# MCU.net
KiCad netlist of a schematic drawn in Altium Designer
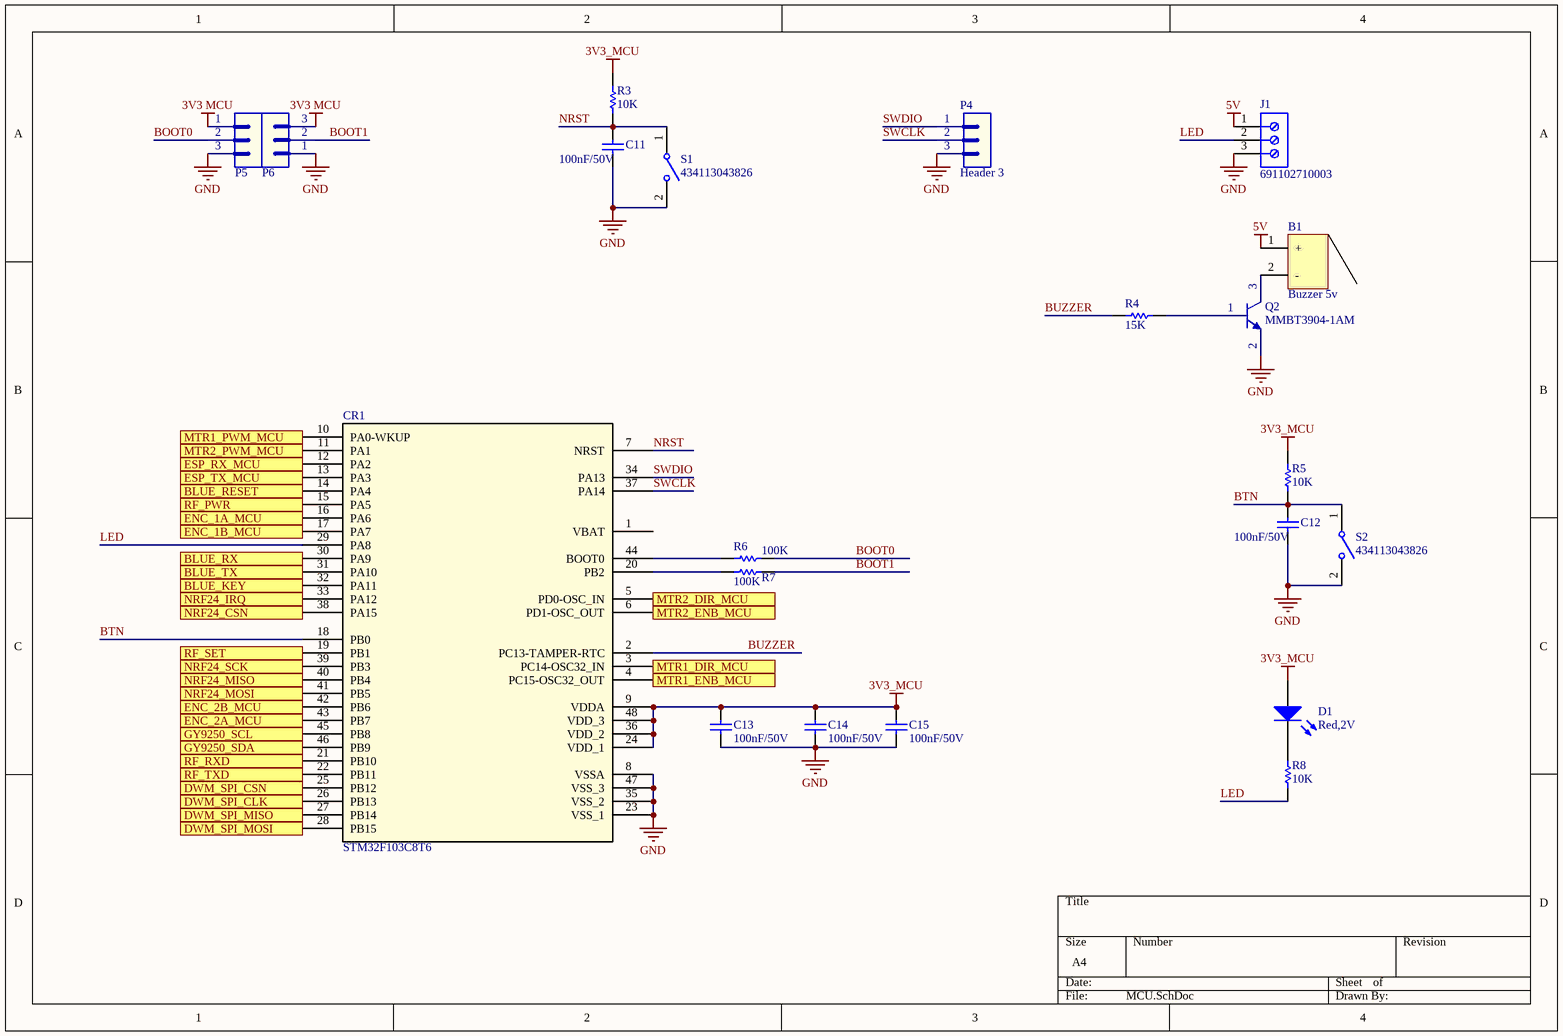
[diagram p0: MCU.SchDoc]

(export (version "E")
  (design (tool "Eeschema 10.0.6"))
  (components
    (comp (ref "B1") (value "Buzzer 5v") (footprint "Buzzer 5v") (libsource (lib "Stm32") (part "Buzzer 5v")))
    (comp (ref "C11")
      (value "100nF/50V")
      (footprint "CAP-SM-0805")
      (description "CAP CER 1000PF 100V X7R 0805")
      (fields
        (field (name "MANUFACTURER") "Johanson Dielectrics Inc.")
        (field (name "MANUFACTURER PART NUMBER") "101X15W102MV4E")
      )
      (libsource (lib "Capacitor") (part "Cap-1nF-50V-0805"))
    )
    (comp (ref "C12")
      (value "100nF/50V")
      (footprint "CAP-SM-0805")
      (description "CAP CER 1000PF 100V X7R 0805")
      (fields
        (field (name "MANUFACTURER") "Johanson Dielectrics Inc.")
        (field (name "MANUFACTURER PART NUMBER") "101X15W102MV4E")
      )
      (libsource (lib "Capacitor") (part "Cap-1nF-50V-0805"))
    )
    (comp (ref "C13")
      (value "100nF/50V")
      (footprint "CAP-SM-0805")
      (description "CAP CER 1000PF 100V X7R 0805")
      (fields
        (field (name "MANUFACTURER") "Johanson Dielectrics Inc.")
        (field (name "MANUFACTURER PART NUMBER") "101X15W102MV4E")
      )
      (libsource (lib "Capacitor") (part "Cap-1nF-50V-0805"))
    )
    (comp (ref "C14")
      (value "100nF/50V")
      (footprint "CAP-SM-0805")
      (description "CAP CER 1000PF 100V X7R 0805")
      (fields
        (field (name "MANUFACTURER") "Johanson Dielectrics Inc.")
        (field (name "MANUFACTURER PART NUMBER") "101X15W102MV4E")
      )
      (libsource (lib "Capacitor") (part "Cap-1nF-50V-0805"))
    )
    (comp (ref "C15")
      (value "100nF/50V")
      (footprint "CAP-SM-0805")
      (description "CAP CER 1000PF 100V X7R 0805")
      (fields
        (field (name "MANUFACTURER") "Johanson Dielectrics Inc.")
        (field (name "MANUFACTURER PART NUMBER") "101X15W102MV4E")
      )
      (libsource (lib "Capacitor") (part "Cap-1nF-50V-0805"))
    )
    (comp (ref "CR1")
      (value "STM32F103C8T6")
      (footprint "STM32F103C8T6")
      (fields (field (name "COPYRIGHT") "Copyright (C) 2018 Accelerated Designs. All rights reserved"))
      (libsource (lib "Schlib1") (part "STM32F103C8T6"))
    )
    (comp (ref "D1")
      (value "Red,2V")
      (footprint "LED-3mm")
      (description "LED RED CLEAR T-1 T/H")
      (fields
        (field (name "MANUFACTURER") "Kingbright")
        (field (name "MANUFACTURER PART NUMBER") "WP710A10SEC/J3")
      )
      (libsource (lib "LED") (part "LED-RED-TH-3mm"))
    )
    (comp (ref "J1")
      (value "691102710003")
      (footprint "691102710003")
      (description "WR-TBL Serie 102 Horizontal Entry Modular, Pressure Clamp, pitch 5mm, 3p")
      (fields (field (name "PUBLISHER") "Wurth Elektronik"))
      (libsource (lib "691101710002_Altium_WR-TBL_rev19a") (part "691102710003"))
    )
    (comp (ref "P4")
      (value "Header 3")
      (footprint "jp3")
      (description "Header, 3-Pin")
      (fields (field (name "PUBLISHER") "Altium Limited"))
      (libsource (lib "") (part "Header 3_1"))
    )
    (comp (ref "P5")
      (value "~")
      (footprint "jp3")
      (description "Header, 3-Pin")
      (fields (field (name "PUBLISHER") "Altium Limited"))
      (libsource (lib "") (part "Header 3_1"))
    )
    (comp (ref "P6")
      (value "~")
      (footprint "jp3")
      (description "Header, 3-Pin")
      (fields (field (name "PUBLISHER") "Altium Limited"))
      (libsource (lib "Integrated_Library_Test") (part "Header 3"))
    )
    (comp (ref "Q2")
      (value "MMBT3904-1AM")
      (footprint "SOT23_NEX")
      (libsource (lib "BJT") (part "MMBT3904-1AM"))
    )
    (comp (ref "R3")
      (value "10K")
      (footprint "Resistor:RES-SM-0805")
      (description "RES 0 OHM JUMPER 0805")
      (fields
        (field (name "MANUFACTURER") "Vishay Dale")
        (field (name "MANUFACTURER PART NUMBER") "WSL080500000ZEA9")
      )
      (libsource (lib "Resistor") (part "Res-0-0805"))
    )
    (comp (ref "R4")
      (value "15K")
      (footprint "Resistor:RES-SM-0805")
      (description "RES 12 KOHM JUMPER 0805")
      (fields
        (field (name "MANUFACTURER") "Vishay Thin Film")
        (field (name "MANUFACTURER PART NUMBER") "PAT0805E3121BST1")
      )
      (libsource (lib "Resistor") (part "Res-12K-0805"))
    )
    (comp (ref "R5")
      (value "10K")
      (footprint "Resistor:RES-SM-0805")
      (description "RES 0 OHM JUMPER 0805")
      (fields
        (field (name "MANUFACTURER") "Vishay Dale")
        (field (name "MANUFACTURER PART NUMBER") "WSL080500000ZEA9")
      )
      (libsource (lib "Resistor") (part "Res-0-0805"))
    )
    (comp (ref "R6")
      (value "100K")
      (footprint "Resistor:RES-SM-0805")
      (description "RES 1K OHM 1% 1/4W 0805")
      (fields
        (field (name "MANUFACTURER") "Stackpole Electronics Inc")
        (field (name "MANUFACTURER PART NUMBER") "RNCP0805FTD1K00")
      )
      (libsource (lib "Resistor") (part "Res-1K-0805"))
    )
    (comp (ref "R7")
      (value "100K")
      (footprint "Resistor:RES-SM-0805")
      (description "RES 1K OHM 1% 1/4W 0805")
      (fields
        (field (name "MANUFACTURER") "Stackpole Electronics Inc")
        (field (name "MANUFACTURER PART NUMBER") "RNCP0805FTD1K00")
      )
      (libsource (lib "Resistor") (part "Res-1K-0805"))
    )
    (comp (ref "R8")
      (value "10K")
      (footprint "Resistor:RES-SM-0805")
      (description "RES 0 OHM JUMPER 0805")
      (fields
        (field (name "MANUFACTURER") "Vishay Dale")
        (field (name "MANUFACTURER PART NUMBER") "WSL080500000ZEA9")
      )
      (libsource (lib "Resistor") (part "Res-0-0805"))
    )
    (comp (ref "S1")
      (value "434113043826")
      (footprint "434113043826")
      (description "WS-TASV J-Bend SMT Tact Switch 6x3.5mm, height 4.3mm, 260gf")
      (fields (field (name "PUBLISHER") "Wurth Elektronik"))
      (libsource (lib "434113043826_Altium_WS-TASV_rev20a") (part "434113043826"))
    )
    (comp (ref "S2")
      (value "434113043826")
      (footprint "434113043826")
      (description "WS-TASV J-Bend SMT Tact Switch 6x3.5mm, height 4.3mm, 260gf")
      (fields (field (name "PUBLISHER") "Wurth Elektronik"))
      (libsource (lib "434113043826_Altium_WS-TASV_rev20a") (part "434113043826"))
    )
  )
  (nets
    (net (code "1") (name "/BLUE_KEY") (class "Default")
      (node (ref "CR1") (pin "32") (pinfunction "PA11_32") (pintype "open_collector"))
    )
    (net (code "2") (name "/BLUE_RESET") (class "Default")
      (node (ref "CR1") (pin "14") (pinfunction "PA4_14") (pintype "open_collector"))
    )
    (net (code "3") (name "/BLUE_RX") (class "Default")
      (node (ref "CR1") (pin "30") (pinfunction "PA9_30") (pintype "open_collector"))
    )
    (net (code "4") (name "/BLUE_TX") (class "Default")
      (node (ref "CR1") (pin "31") (pinfunction "PA10_31") (pintype "open_collector"))
    )
    (net (code "5") (name "/BOOT0") (class "Default")
      (node (ref "P5") (pin "2") (pinfunction "2_2") (pintype "passive"))
      (node (ref "R6") (pin "2") (pinfunction "2_2") (pintype "passive"))
    )
    (net (code "6") (name "/BOOT1") (class "Default")
      (node (ref "P6") (pin "2") (pinfunction "2_2") (pintype "passive"))
      (node (ref "R7") (pin "2") (pinfunction "2_2") (pintype "passive"))
    )
    (net (code "7") (name "/BTN") (class "Default")
      (node (ref "C12") (pin "2") (pinfunction "2_2") (pintype "passive"))
      (node (ref "CR1") (pin "18") (pinfunction "PB0_18") (pintype "open_collector"))
      (node (ref "R5") (pin "1") (pinfunction "1_1") (pintype "passive"))
      (node (ref "S2") (pin "1") (pinfunction "1_1") (pintype "passive"))
    )
    (net (code "8") (name "/BUZZER") (class "Default")
      (node (ref "CR1") (pin "2") (pinfunction "PC13-TAMPER-RTC_2") (pintype "open_collector"))
      (node (ref "R4") (pin "1") (pinfunction "1_1") (pintype "passive"))
    )
    (net (code "9") (name "/DWM_SPI_CLK") (class "Default")
      (node (ref "CR1") (pin "26") (pinfunction "PB13_26") (pintype "open_collector"))
    )
    (net (code "10") (name "/DWM_SPI_CSN") (class "Default")
      (node (ref "CR1") (pin "25") (pinfunction "PB12_25") (pintype "open_collector"))
    )
    (net (code "11") (name "/DWM_SPI_MISO") (class "Default")
      (node (ref "CR1") (pin "27") (pinfunction "PB14_27") (pintype "open_collector"))
    )
    (net (code "12") (name "/DWM_SPI_MOSI") (class "Default")
      (node (ref "CR1") (pin "28") (pinfunction "PB15_28") (pintype "open_collector"))
    )
    (net (code "13") (name "/ENC_1A_MCU") (class "Default")
      (node (ref "CR1") (pin "16") (pinfunction "PA6_16") (pintype "open_collector"))
    )
    (net (code "14") (name "/ENC_1B_MCU") (class "Default")
      (node (ref "CR1") (pin "17") (pinfunction "PA7_17") (pintype "open_collector"))
    )
    (net (code "15") (name "/ENC_2A_MCU") (class "Default")
      (node (ref "CR1") (pin "43") (pinfunction "PB7_43") (pintype "open_collector"))
    )
    (net (code "16") (name "/ENC_2B_MCU") (class "Default")
      (node (ref "CR1") (pin "42") (pinfunction "PB6_42") (pintype "open_collector"))
    )
    (net (code "17") (name "/ESP_RX_MCU") (class "Default")
      (node (ref "CR1") (pin "12") (pinfunction "PA2_12") (pintype "open_collector"))
    )
    (net (code "18") (name "/ESP_TX_MCU") (class "Default")
      (node (ref "CR1") (pin "13") (pinfunction "PA3_13") (pintype "open_collector"))
    )
    (net (code "19") (name "/GY9250_SCL") (class "Default")
      (node (ref "CR1") (pin "45") (pinfunction "PB8_45") (pintype "open_collector"))
    )
    (net (code "20") (name "/GY9250_SDA") (class "Default")
      (node (ref "CR1") (pin "46") (pinfunction "PB9_46") (pintype "open_collector"))
    )
    (net (code "21") (name "/LED") (class "Default")
      (node (ref "CR1") (pin "29") (pinfunction "PA8_29") (pintype "open_collector"))
      (node (ref "J1") (pin "2") (pinfunction "2_2") (pintype "passive"))
      (node (ref "R8") (pin "1") (pinfunction "1_1") (pintype "passive"))
    )
    (net (code "22") (name "/MTR1_DIR_MCU") (class "Default")
      (node (ref "CR1") (pin "3") (pinfunction "PC14-OSC32_IN_3") (pintype "open_collector"))
    )
    (net (code "23") (name "/MTR1_ENB_MCU") (class "Default")
      (node (ref "CR1") (pin "4") (pinfunction "PC15-OSC32_OUT_4") (pintype "open_collector"))
    )
    (net (code "24") (name "/MTR1_PWM_MCU") (class "Default")
      (node (ref "CR1") (pin "10") (pinfunction "PA0-WKUP_10") (pintype "open_collector"))
    )
    (net (code "25") (name "/MTR2_DIR_MCU") (class "Default")
      (node (ref "CR1") (pin "5") (pinfunction "PD0-OSC_IN_5") (pintype "open_collector"))
    )
    (net (code "26") (name "/MTR2_ENB_MCU") (class "Default")
      (node (ref "CR1") (pin "6") (pinfunction "PD1-OSC_OUT_6") (pintype "open_collector"))
    )
    (net (code "27") (name "/MTR2_PWM_MCU") (class "Default")
      (node (ref "CR1") (pin "11") (pinfunction "PA1_11") (pintype "open_collector"))
    )
    (net (code "28") (name "/NRF24_CSN") (class "Default")
      (node (ref "CR1") (pin "38") (pinfunction "PA15_38") (pintype "open_collector"))
    )
    (net (code "29") (name "/NRF24_IRQ") (class "Default")
      (node (ref "CR1") (pin "33") (pinfunction "PA12_33") (pintype "open_collector"))
    )
    (net (code "30") (name "/NRF24_MISO") (class "Default")
      (node (ref "CR1") (pin "40") (pinfunction "PB4_40") (pintype "open_collector"))
    )
    (net (code "31") (name "/NRF24_MOSI") (class "Default")
      (node (ref "CR1") (pin "41") (pinfunction "PB5_41") (pintype "open_collector"))
    )
    (net (code "32") (name "/NRF24_SCK") (class "Default")
      (node (ref "CR1") (pin "39") (pinfunction "PB3_39") (pintype "open_collector"))
    )
    (net (code "33") (name "/NRST") (class "Default")
      (node (ref "C11") (pin "2") (pinfunction "2_2") (pintype "passive"))
      (node (ref "CR1") (pin "7") (pinfunction "NRST_7") (pintype "open_collector"))
      (node (ref "R3") (pin "1") (pinfunction "1_1") (pintype "passive"))
      (node (ref "S1") (pin "1") (pinfunction "1_1") (pintype "passive"))
    )
    (net (code "34") (name "/RF_PWR") (class "Default")
      (node (ref "CR1") (pin "15") (pinfunction "PA5_15") (pintype "open_collector"))
    )
    (net (code "35") (name "/RF_RXD") (class "Default")
      (node (ref "CR1") (pin "21") (pinfunction "PB10_21") (pintype "open_collector"))
    )
    (net (code "36") (name "/RF_SET") (class "Default")
      (node (ref "CR1") (pin "19") (pinfunction "PB1_19") (pintype "open_collector"))
    )
    (net (code "37") (name "/RF_TXD") (class "Default")
      (node (ref "CR1") (pin "22") (pinfunction "PB11_22") (pintype "open_collector"))
    )
    (net (code "38") (name "/SWCLK") (class "Default")
      (node (ref "CR1") (pin "37") (pinfunction "PA14_37") (pintype "open_collector"))
      (node (ref "P4") (pin "2") (pinfunction "2_2") (pintype "passive"))
    )
    (net (code "39") (name "/SWDIO") (class "Default")
      (node (ref "CR1") (pin "34") (pinfunction "PA13_34") (pintype "open_collector"))
      (node (ref "P4") (pin "1") (pinfunction "1_1") (pintype "passive"))
    )
    (net (code "40") (name "3V3 MCU") (class "Default")
      (node (ref "P5") (pin "1") (pinfunction "1_1") (pintype "passive"))
      (node (ref "P6") (pin "3") (pinfunction "3_3") (pintype "passive"))
    )
    (net (code "41") (name "3V3_MCU") (class "Default")
      (node (ref "C13") (pin "2") (pinfunction "2_2") (pintype "passive"))
      (node (ref "C14") (pin "2") (pinfunction "2_2") (pintype "passive"))
      (node (ref "C15") (pin "2") (pinfunction "2_2") (pintype "passive"))
      (node (ref "CR1") (pin "24") (pinfunction "VDD_1_24") (pintype "open_collector"))
      (node (ref "CR1") (pin "36") (pinfunction "VDD_2_36") (pintype "open_collector"))
      (node (ref "CR1") (pin "48") (pinfunction "VDD_3_48") (pintype "open_collector"))
      (node (ref "CR1") (pin "9") (pinfunction "VDDA_9") (pintype "open_collector"))
      (node (ref "D1") (pin "1") (pinfunction "A_1") (pintype "passive"))
      (node (ref "R3") (pin "2") (pinfunction "2_2") (pintype "passive"))
      (node (ref "R5") (pin "2") (pinfunction "2_2") (pintype "passive"))
    )
    (net (code "42") (name "5V") (class "Default")
      (node (ref "B1") (pin "1") (pinfunction "+_1") (pintype "passive"))
      (node (ref "J1") (pin "1") (pinfunction "1_1") (pintype "passive"))
    )
    (net (code "43") (name "GND") (class "Default")
      (node (ref "C11") (pin "1") (pinfunction "1_1") (pintype "passive"))
      (node (ref "C12") (pin "1") (pinfunction "1_1") (pintype "passive"))
      (node (ref "C13") (pin "1") (pinfunction "1_1") (pintype "passive"))
      (node (ref "C14") (pin "1") (pinfunction "1_1") (pintype "passive"))
      (node (ref "C15") (pin "1") (pinfunction "1_1") (pintype "passive"))
      (node (ref "CR1") (pin "23") (pinfunction "VSS_1_23") (pintype "open_collector"))
      (node (ref "CR1") (pin "35") (pinfunction "VSS_2_35") (pintype "open_collector"))
      (node (ref "CR1") (pin "47") (pinfunction "VSS_3_47") (pintype "open_collector"))
      (node (ref "CR1") (pin "8") (pinfunction "VSSA_8") (pintype "open_collector"))
      (node (ref "J1") (pin "3") (pinfunction "3_3") (pintype "passive"))
      (node (ref "P4") (pin "3") (pinfunction "3_3") (pintype "passive"))
      (node (ref "P5") (pin "3") (pinfunction "3_3") (pintype "passive"))
      (node (ref "P6") (pin "1") (pinfunction "1_1") (pintype "passive"))
      (node (ref "Q2") (pin "2") (pinfunction "E_2") (pintype "passive"))
      (node (ref "S1") (pin "2") (pinfunction "2_2") (pintype "passive"))
      (node (ref "S2") (pin "2") (pinfunction "2_2") (pintype "passive"))
    )
    (net (code "44") (name "Net-(B1--)") (class "Default")
      (node (ref "B1") (pin "2") (pinfunction "-_2") (pintype "passive"))
      (node (ref "Q2") (pin "3") (pinfunction "C_3") (pintype "passive"))
    )
    (net (code "45") (name "Net-(CR1-BOOT0)") (class "Default")
      (node (ref "CR1") (pin "44") (pinfunction "BOOT0_44") (pintype "open_collector"))
      (node (ref "R6") (pin "1") (pinfunction "1_1") (pintype "passive"))
    )
    (net (code "46") (name "Net-(CR1-PB2)") (class "Default")
      (node (ref "CR1") (pin "20") (pinfunction "PB2_20") (pintype "open_collector"))
      (node (ref "R7") (pin "1") (pinfunction "1_1") (pintype "passive"))
    )
    (net (code "47") (name "Net-(D1-K)") (class "Default")
      (node (ref "D1") (pin "2") (pinfunction "K_2") (pintype "passive"))
      (node (ref "R8") (pin "2") (pinfunction "2_2") (pintype "passive"))
    )
    (net (code "48") (name "Net-(Q2-B)") (class "Default")
      (node (ref "Q2") (pin "1") (pinfunction "B_1") (pintype "passive"))
      (node (ref "R4") (pin "2") (pinfunction "2_2") (pintype "passive"))
    )
    (net (code "49") (name "unconnected-(CR1-VBAT-Pad1)") (class "Default")
      (node (ref "CR1") (pin "1") (pinfunction "VBAT_1") (pintype "open_collector"))
    )
  )
)
